# Wattuino-Nanite841_v10.net
KiCad netlist of a schematic drawn in EAGLE
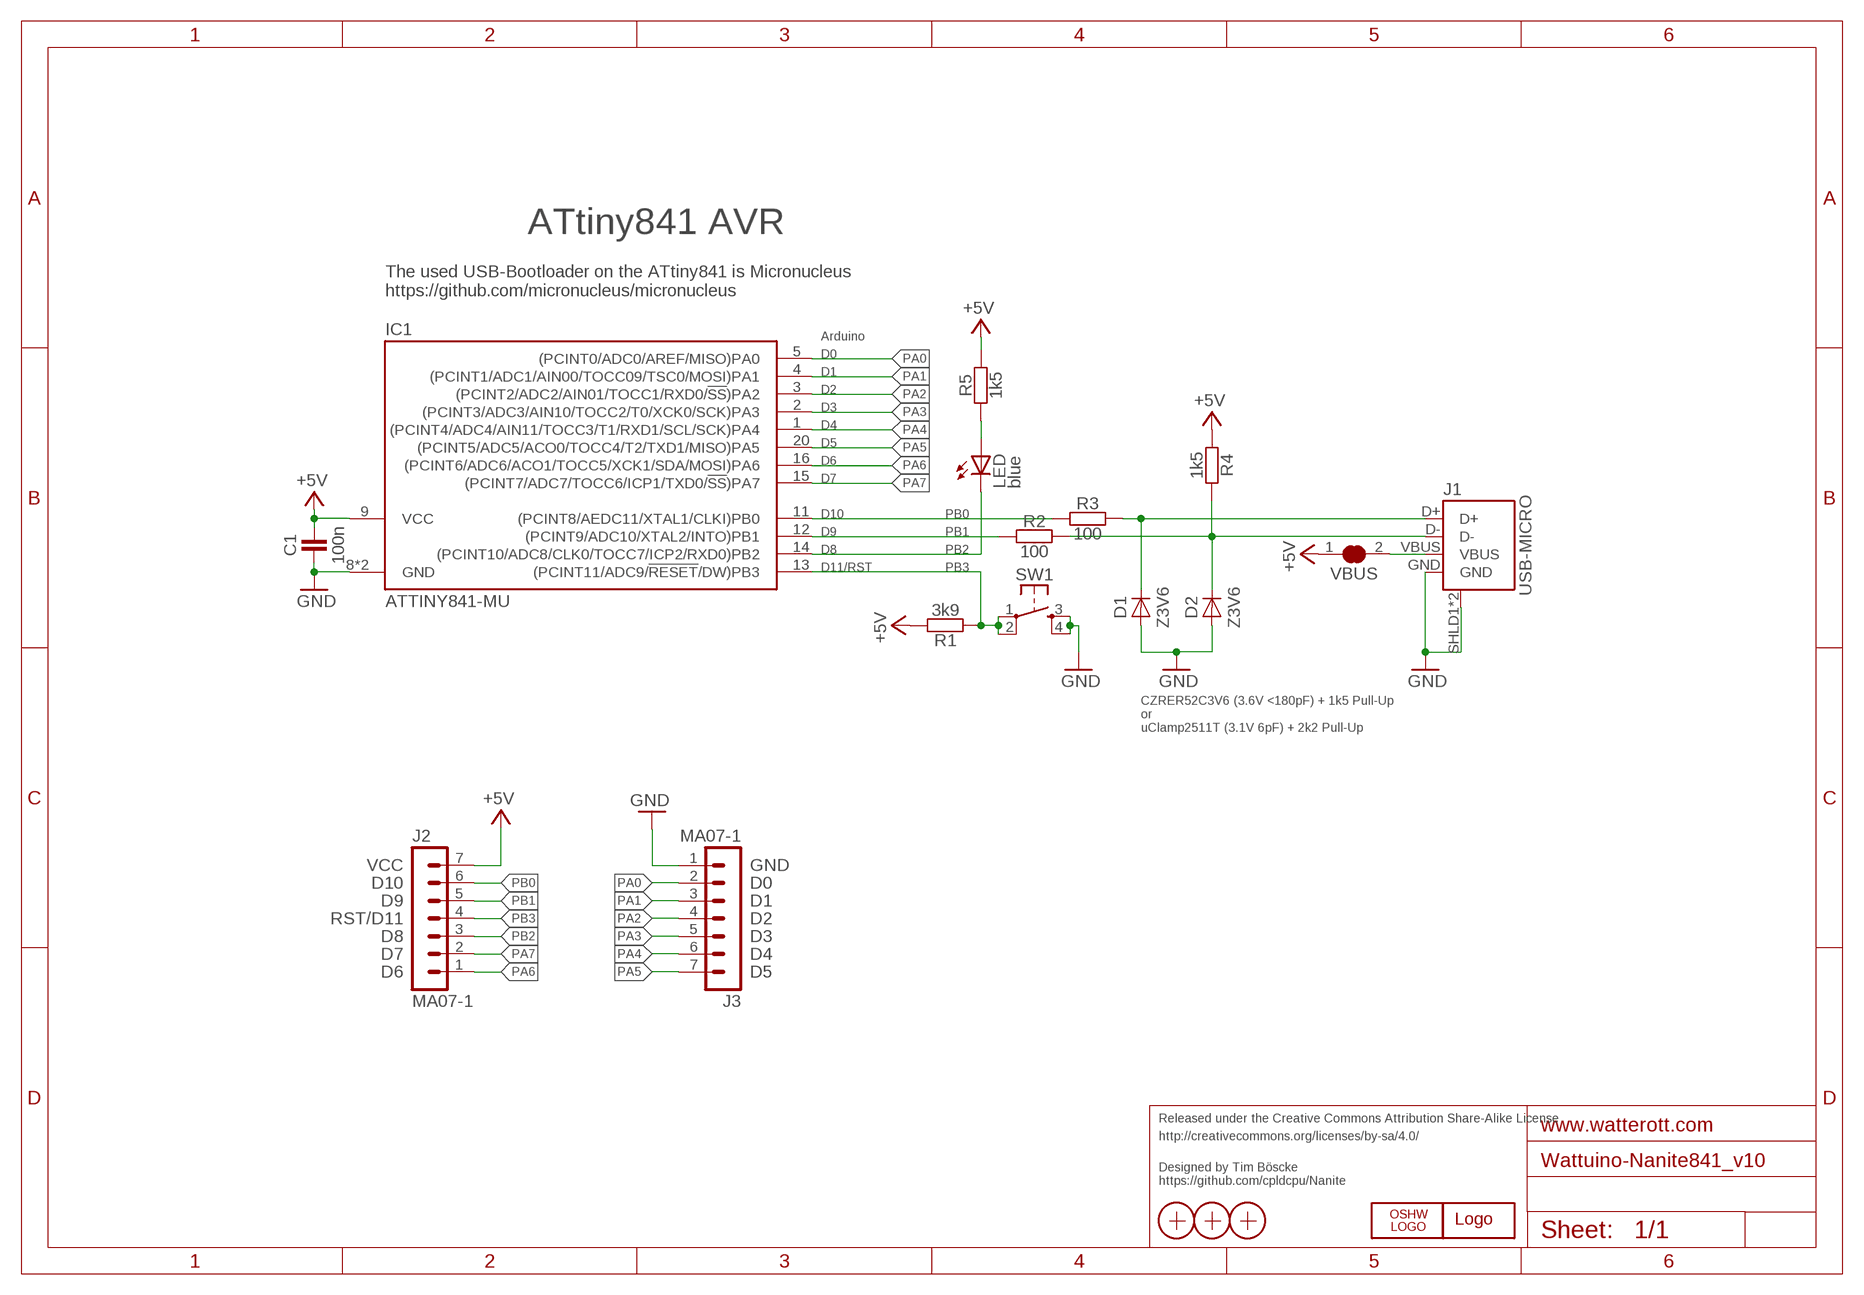
[diagram p0: schematic, sheet 1]

(export (version "E")
  (design (tool "Eeschema 10.0.6"))
  (components
    (comp (ref "C1")
      (value "100n")
      (footprint "eagle-import:C0402")
      (libsource (lib "eagle-import") (part "CAPACITOR-0402"))
    )
    (comp (ref "D1")
      (value "Z3V6")
      (footprint "eagle-import:SOD882")
      (libsource (lib "eagle-import") (part "DIODE-SOD882"))
    )
    (comp (ref "D2")
      (value "Z3V6")
      (footprint "eagle-import:SOD882")
      (libsource (lib "eagle-import") (part "DIODE-SOD882"))
    )
    (comp (ref "IC1")
      (value "ATTINY841-MU")
      (footprint "eagle-import:QFN20-PAD")
      (libsource (lib "eagle-import") (part "ATTINY841-MU"))
    )
    (comp (ref "J1")
      (value "USB-MICRO")
      (footprint "eagle-import:USB-MICRO-10103594")
      (libsource (lib "eagle-import") (part "USB-MICRO"))
    )
    (comp (ref "J2")
      (value "MA07-1")
      (footprint "eagle-import:MA07-1")
      (libsource (lib "eagle-import") (part "MA07-1"))
    )
    (comp (ref "J3")
      (value "MA07-1")
      (footprint "eagle-import:MA07-1")
      (libsource (lib "eagle-import") (part "MA07-1"))
    )
    (comp (ref "LED")
      (value "blue")
      (footprint "eagle-import:C0603")
      (libsource (lib "eagle-import") (part "LED-0603"))
    )
    (comp (ref "LOGO1")
      (value "LOGO-S_PLACE_S")
      (footprint "eagle-import:SPARK_TPLACE_S")
      (libsource (lib "eagle-import") (part "LOGO-S_PLACE_S"))
    )
    (comp (ref "LOGO2")
      (value "OSHW_LOGOX0070")
      (footprint "eagle-import:OSHW_6X70")
      (libsource (lib "eagle-import") (part "OSHW_LOGOX0070"))
    )
    (comp (ref "R1")
      (value "3k9")
      (footprint "eagle-import:C0402")
      (libsource (lib "eagle-import") (part "RESISTOR-0402"))
    )
    (comp (ref "R2")
      (value "100")
      (footprint "eagle-import:C0402")
      (libsource (lib "eagle-import") (part "RESISTOR-0402"))
    )
    (comp (ref "R3")
      (value "100")
      (footprint "eagle-import:C0402")
      (libsource (lib "eagle-import") (part "RESISTOR-0402"))
    )
    (comp (ref "R4")
      (value "1k5")
      (footprint "eagle-import:C0402")
      (libsource (lib "eagle-import") (part "RESISTOR-0402"))
    )
    (comp (ref "R5")
      (value "1k5")
      (footprint "eagle-import:C0402")
      (libsource (lib "eagle-import") (part "RESISTOR-0402"))
    )
    (comp (ref "SW1")
      (value "SW-TACTILE-PTS840P")
      (footprint "eagle-import:SW_PTS840P")
      (libsource (lib "eagle-import") (part "SW-TACTILE-PTS840P"))
    )
    (comp (ref "VBUS")
      (value "JUMPER2-0603-NC")
      (footprint "eagle-import:JUMPER2-0603_NC")
      (libsource (lib "eagle-import") (part "JUMPER2-0603-NC"))
    )
    (comp (ref "X1")
      (value "PASSER-07")
      (footprint "eagle-import:PASSER_07MM")
      (libsource (lib "eagle-import") (part "PASSER-07"))
    )
    (comp (ref "X2")
      (value "PASSER-07")
      (footprint "eagle-import:PASSER_07MM")
      (libsource (lib "eagle-import") (part "PASSER-07"))
    )
    (comp (ref "X3")
      (value "PASSER-07")
      (footprint "eagle-import:PASSER_07MM")
      (libsource (lib "eagle-import") (part "PASSER-07"))
    )
  )
  (nets
    (net (code "1") (name "+5V") (class "Default")
      (node (ref "C1") (pin "2") (pinfunction "2_2") (pintype "passive"))
      (node (ref "IC1") (pin "9") (pinfunction "VCC_9") (pintype "power_in"))
      (node (ref "J2") (pin "7") (pinfunction "7_7") (pintype "passive"))
      (node (ref "R1") (pin "2") (pinfunction "2_2") (pintype "passive"))
      (node (ref "R4") (pin "1") (pinfunction "1_1") (pintype "passive"))
      (node (ref "R5") (pin "2") (pinfunction "2_2") (pintype "passive"))
      (node (ref "VBUS") (pin "1") (pinfunction "1_1") (pintype "passive"))
    )
    (net (code "2") (name "GND") (class "Default")
      (node (ref "C1") (pin "1") (pinfunction "1_1") (pintype "passive"))
      (node (ref "D1") (pin "A") (pinfunction "A_A") (pintype "passive"))
      (node (ref "D2") (pin "A") (pinfunction "A_A") (pintype "passive"))
      (node (ref "IC1") (pin "8") (pinfunction "GND_8") (pintype "power_in"))
      (node (ref "IC1") (pin "TP") (pinfunction "GND_TP") (pintype "power_in"))
      (node (ref "J1") (pin "GND") (pinfunction "GND_GND") (pintype "power_in"))
      (node (ref "J1") (pin "SHLD1") (pinfunction "SHIELD_SHLD1") (pintype "passive"))
      (node (ref "J1") (pin "SHLD2") (pinfunction "SHIELD_SHLD2") (pintype "passive"))
      (node (ref "J3") (pin "1") (pinfunction "1_1") (pintype "passive"))
      (node (ref "SW1") (pin "3") (pinfunction "S1_3") (pintype "passive"))
      (node (ref "SW1") (pin "4") (pinfunction "S2_4") (pintype "passive"))
    )
    (net (code "3") (name "Net-(D1-PadC)") (class "Default")
      (node (ref "D1") (pin "C") (pinfunction "C_C") (pintype "passive"))
      (node (ref "J1") (pin "D+") (pinfunction "D+_D+") (pintype "bidirectional"))
      (node (ref "R3") (pin "2") (pinfunction "2_2") (pintype "passive"))
    )
    (net (code "4") (name "Net-(D2-PadC)") (class "Default")
      (node (ref "D2") (pin "C") (pinfunction "C_C") (pintype "passive"))
      (node (ref "J1") (pin "D-") (pinfunction "D-_D-") (pintype "bidirectional"))
      (node (ref "R2") (pin "2") (pinfunction "2_2") (pintype "passive"))
      (node (ref "R4") (pin "2") (pinfunction "2_2") (pintype "passive"))
    )
    (net (code "5") (name "Net-(J1-PadVBUS)") (class "Default")
      (node (ref "J1") (pin "VBUS") (pinfunction "VBUS_VBUS") (pintype "power_in"))
      (node (ref "VBUS") (pin "2") (pinfunction "2_2") (pintype "passive"))
    )
    (net (code "6") (name "Net-(LED-PadA)") (class "Default")
      (node (ref "LED") (pin "A") (pinfunction "A_A") (pintype "passive"))
      (node (ref "R5") (pin "1") (pinfunction "1_1") (pintype "passive"))
    )
    (net (code "7") (name "PA0") (class "Default")
      (node (ref "IC1") (pin "5") (pinfunction "(PCINT0/ADC0/AREF/MISO)PA0_5") (pintype "bidirectional"))
      (node (ref "J3") (pin "2") (pinfunction "2_2") (pintype "passive"))
    )
    (net (code "8") (name "PA1") (class "Default")
      (node (ref "IC1") (pin "4") (pinfunction "(PCINT1/ADC1/AIN00/TOCC09/TSC0/MOSI)PA1_4") (pintype "bidirectional"))
      (node (ref "J3") (pin "3") (pinfunction "3_3") (pintype "passive"))
    )
    (net (code "9") (name "PA2") (class "Default")
      (node (ref "IC1") (pin "3") (pinfunction "(PCINT2/ADC2/AIN01/TOCC1/RXD0/~{SS})PA2_3") (pintype "bidirectional"))
      (node (ref "J3") (pin "4") (pinfunction "4_4") (pintype "passive"))
    )
    (net (code "10") (name "PA3") (class "Default")
      (node (ref "IC1") (pin "2") (pinfunction "(PCINT3/ADC3/AIN10/TOCC2/T0/XCK0/SCK)PA3_2") (pintype "bidirectional"))
      (node (ref "J3") (pin "5") (pinfunction "5_5") (pintype "passive"))
    )
    (net (code "11") (name "PA4") (class "Default")
      (node (ref "IC1") (pin "1") (pinfunction "(PCINT4/ADC4/AIN11/TOCC3/T1/RXD1/SCL/SCK)PA4_1") (pintype "bidirectional"))
      (node (ref "J3") (pin "6") (pinfunction "6_6") (pintype "passive"))
    )
    (net (code "12") (name "PA5") (class "Default")
      (node (ref "IC1") (pin "20") (pinfunction "(PCINT5/ADC5/ACO0/TOCC4/T2/TXD1/MISO)PA5_20") (pintype "bidirectional"))
      (node (ref "J3") (pin "7") (pinfunction "7_7") (pintype "passive"))
    )
    (net (code "13") (name "PA6") (class "Default")
      (node (ref "IC1") (pin "16") (pinfunction "(PCINT6/ADC6/ACO1/TOCC5/XCK1/SDA/MOSI)PA6_16") (pintype "bidirectional"))
      (node (ref "J2") (pin "1") (pinfunction "1_1") (pintype "passive"))
    )
    (net (code "14") (name "PA7") (class "Default")
      (node (ref "IC1") (pin "15") (pinfunction "(PCINT7/ADC7/TOCC6/ICP1/TXD0/~{SS})PA7_15") (pintype "bidirectional"))
      (node (ref "J2") (pin "2") (pinfunction "2_2") (pintype "passive"))
    )
    (net (code "15") (name "PB0") (class "Default")
      (node (ref "IC1") (pin "11") (pinfunction "(PCINT8/AEDC11/XTAL1/CLKI)PB0_11") (pintype "bidirectional"))
      (node (ref "J2") (pin "6") (pinfunction "6_6") (pintype "passive"))
      (node (ref "R3") (pin "1") (pinfunction "1_1") (pintype "passive"))
    )
    (net (code "16") (name "PB1") (class "Default")
      (node (ref "IC1") (pin "12") (pinfunction "(PCINT9/ADC10/XTAL2/INTO)PB1_12") (pintype "bidirectional"))
      (node (ref "J2") (pin "5") (pinfunction "5_5") (pintype "passive"))
      (node (ref "R2") (pin "1") (pinfunction "1_1") (pintype "passive"))
    )
    (net (code "17") (name "PB2") (class "Default")
      (node (ref "IC1") (pin "14") (pinfunction "(PCINT10/ADC8/CLK0/TOCC7/ICP2/RXD0)PB2_14") (pintype "bidirectional"))
      (node (ref "J2") (pin "3") (pinfunction "3_3") (pintype "passive"))
      (node (ref "LED") (pin "C") (pinfunction "C_C") (pintype "passive"))
    )
    (net (code "18") (name "PB3") (class "Default")
      (node (ref "IC1") (pin "13") (pinfunction "(PCINT11/ADC9/~{RESET}/DW)PB3_13") (pintype "bidirectional"))
      (node (ref "J2") (pin "4") (pinfunction "4_4") (pintype "passive"))
      (node (ref "R1") (pin "1") (pinfunction "1_1") (pintype "passive"))
      (node (ref "SW1") (pin "1") (pinfunction "P1_1") (pintype "passive"))
      (node (ref "SW1") (pin "2") (pinfunction "P2_2") (pintype "passive"))
    )
  )
)
